# fonte.net
KiCad netlist of a schematic drawn in EAGLE
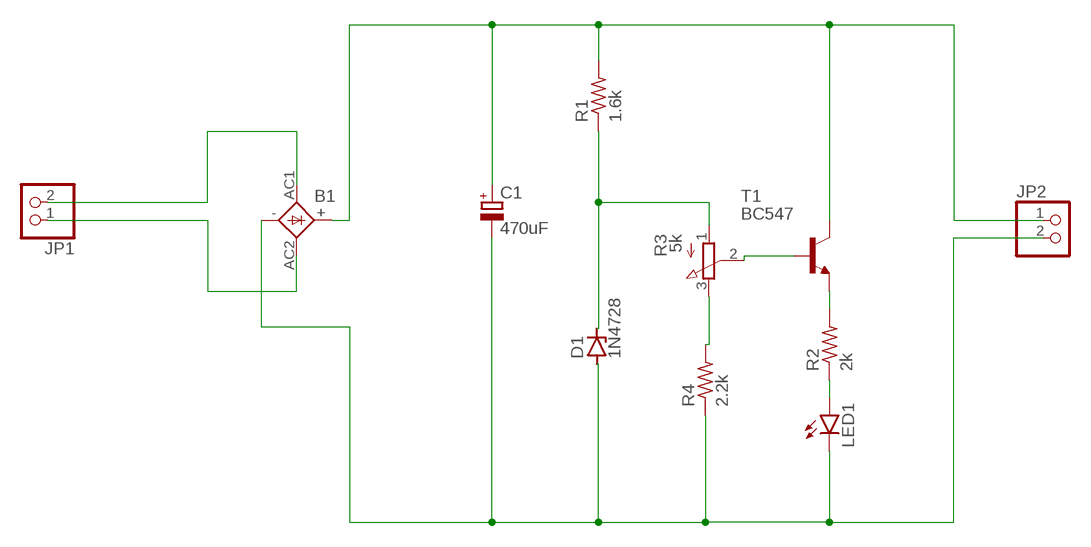
[diagram p0: schematic, sheet 1]

(export (version "E")
  (design (tool "Eeschema 10.0.6"))
  (components
    (comp (ref "B1")
      (value "1KAB")
      (footprint "eagle-import:1KAB")
      (libsource (lib "eagle-import") (part "1KAB"))
    )
    (comp (ref "C1")
      (value "470uF")
      (footprint "eagle-import:E5-10,5")
      (libsource (lib "eagle-import") (part "CPOL-EUE5-10.5"))
    )
    (comp (ref "D1")
      (value "1N4728")
      (footprint "eagle-import:DO41Z10")
      (libsource (lib "eagle-import") (part "1N4728"))
    )
    (comp (ref "JP1")
      (value "PINHD-1X2")
      (footprint "eagle-import:1X02")
      (libsource (lib "eagle-import") (part "PINHD-1X2"))
    )
    (comp (ref "JP2")
      (value "PINHD-1X2")
      (footprint "eagle-import:1X02")
      (libsource (lib "eagle-import") (part "PINHD-1X2"))
    )
    (comp (ref "LED1")
      (value "LED5MM")
      (footprint "eagle-import:LED5MM")
      (libsource (lib "eagle-import") (part "LED5MM"))
    )
    (comp (ref "R1")
      (value "1.6k")
      (footprint "eagle-import:0207_10")
      (libsource (lib "eagle-import") (part "R-US_0207/10"))
    )
    (comp (ref "R2")
      (value "2k")
      (footprint "eagle-import:0207_10")
      (libsource (lib "eagle-import") (part "R-US_0207/10"))
    )
    (comp (ref "R3")
      (value "5k")
      (footprint "eagle-import:3RP_1610N")
      (libsource (lib "eagle-import") (part "3RP/1610N"))
    )
    (comp (ref "R4")
      (value "2.2k")
      (footprint "eagle-import:0207_10")
      (libsource (lib "eagle-import") (part "R-US_0207/10"))
    )
    (comp (ref "T1")
      (value "BC547")
      (footprint "eagle-import:TO92")
      (libsource (lib "eagle-import") (part "BC547"))
    )
  )
  (nets
    (net (code "1") (name "Net-(B1-PadAC1)") (class "Default")
      (node (ref "B1") (pin "AC1") (pinfunction "AC1_AC1") (pintype "passive"))
      (node (ref "JP1") (pin "2") (pinfunction "2_2") (pintype "passive"))
    )
    (net (code "2") (name "Net-(B1-PadAC2)") (class "Default")
      (node (ref "B1") (pin "AC2") (pinfunction "AC2_AC2") (pintype "passive"))
      (node (ref "JP1") (pin "1") (pinfunction "1_1") (pintype "passive"))
    )
    (net (code "3") (name "Net-(LED1-C)") (class "Default")
      (node (ref "B1") (pin "-") (pinfunction "-_-") (pintype "passive"))
      (node (ref "C1") (pin "-") (pinfunction "-_-") (pintype "passive"))
      (node (ref "D1") (pin "A") (pinfunction "A_A") (pintype "passive"))
      (node (ref "JP2") (pin "2") (pinfunction "2_2") (pintype "passive"))
      (node (ref "LED1") (pin "K") (pinfunction "C_K") (pintype "passive"))
      (node (ref "R4") (pin "1") (pinfunction "1_1") (pintype "passive"))
    )
    (net (code "4") (name "Net-(LED1-PadA)") (class "Default")
      (node (ref "LED1") (pin "A") (pinfunction "A_A") (pintype "passive"))
      (node (ref "R2") (pin "1") (pinfunction "1_1") (pintype "passive"))
    )
    (net (code "5") (name "Net-(R3-A)") (class "Default")
      (node (ref "D1") (pin "C") (pinfunction "C_C") (pintype "passive"))
      (node (ref "R1") (pin "1") (pinfunction "1_1") (pintype "passive"))
      (node (ref "R3") (pin "1") (pinfunction "A_1") (pintype "passive"))
    )
    (net (code "6") (name "Net-(R3-E)") (class "Default")
      (node (ref "R3") (pin "3") (pinfunction "E_3") (pintype "passive"))
      (node (ref "R4") (pin "2") (pinfunction "2_2") (pintype "passive"))
    )
    (net (code "7") (name "Net-(R3-S)") (class "Default")
      (node (ref "R3") (pin "2") (pinfunction "S_2") (pintype "passive"))
      (node (ref "T1") (pin "2") (pinfunction "B_2") (pintype "passive"))
    )
    (net (code "8") (name "Net-(T1-C)") (class "Default")
      (node (ref "B1") (pin "+") (pinfunction "+_+") (pintype "passive"))
      (node (ref "C1") (pin "+") (pinfunction "+_+") (pintype "passive"))
      (node (ref "JP2") (pin "1") (pinfunction "1_1") (pintype "passive"))
      (node (ref "R1") (pin "2") (pinfunction "2_2") (pintype "passive"))
      (node (ref "T1") (pin "3") (pinfunction "C_3") (pintype "passive"))
    )
    (net (code "9") (name "Net-(T1-E)") (class "Default")
      (node (ref "R2") (pin "2") (pinfunction "2_2") (pintype "passive"))
      (node (ref "T1") (pin "1") (pinfunction "E_1") (pintype "passive"))
    )
  )
)
